# GPIO_Expander.net
KiCad netlist of a schematic drawn in Altium Designer
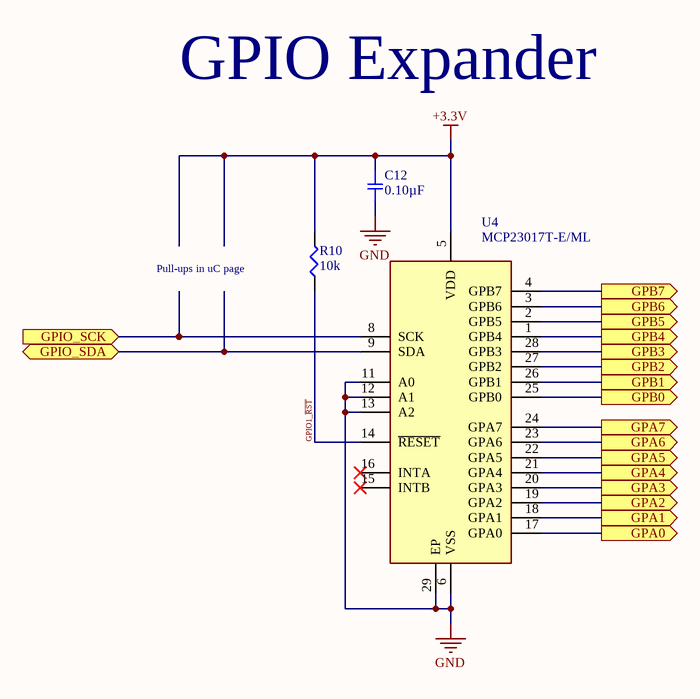
[diagram p0: GPIO_Expander.SchDoc]

(export (version "E")
  (design (tool "Eeschema 10.0.6"))
  (components
    (comp (ref "C12")
      (value "0.10µF")
      (footprint "SMD-0402C")
      (description "CAP CER 0.1UF 16V X7R 0402")
      (fields
        (field (name "DIGI-KEY PART NUMBER") "490-4759-1-ND")
        (field (name "PART NUMBER") "GCM155R71C104KA55D")
      )
      (libsource (lib "capacitor_murata_0402") (part "GCM155R71C104KA55D"))
    )
    (comp (ref "R10")
      (value "10k")
      (footprint "SMD-0402-RES")
      (description "RES SMD 10K OHM 1% 1/10W 0402")
      (fields
        (field (name "PART NUMBER") "ERJ-2RKF1002X")
        (field (name "DIGI-KEY PART NUMBER") "P10.0KLCT-ND")
      )
      (libsource (lib "Panasonic_ERJ_0402") (part "ERJ-2RKF1002X"))
    )
    (comp (ref "U4")
      (value "MCP23017T-E/ML")
      (footprint "QFN65P600X600X100-29N-D")
      (description "Interface - I/O Expanders 16bit Input/Output Exp I2C interface")
      (fields (field (name "MOUSER PART NUMBER") "579-MCP23017T-E/ML"))
      (libsource (lib "SomoPowerPackControl") (part "MCP23017T-E/ML"))
    )
  )
  (nets
    (net (code "1") (name "+3.3V") (class "Default")
      (node (ref "C12") (pin "1") (pinfunction "1_1") (pintype "passive"))
      (node (ref "R10") (pin "2") (pinfunction "2_2") (pintype "passive"))
      (node (ref "U4") (pin "5") (pinfunction "VDD_5") (pintype "passive"))
    )
    (net (code "2") (name "/GPA0") (class "Default")
      (node (ref "U4") (pin "17") (pinfunction "GPA0_17") (pintype "passive"))
    )
    (net (code "3") (name "/GPA1") (class "Default")
      (node (ref "U4") (pin "18") (pinfunction "GPA1_18") (pintype "passive"))
    )
    (net (code "4") (name "/GPA2") (class "Default")
      (node (ref "U4") (pin "19") (pinfunction "GPA2_19") (pintype "passive"))
    )
    (net (code "5") (name "/GPA3") (class "Default")
      (node (ref "U4") (pin "20") (pinfunction "GPA3_20") (pintype "passive"))
    )
    (net (code "6") (name "/GPA4") (class "Default")
      (node (ref "U4") (pin "21") (pinfunction "GPA4_21") (pintype "passive"))
    )
    (net (code "7") (name "/GPA5") (class "Default")
      (node (ref "U4") (pin "22") (pinfunction "GPA5_22") (pintype "passive"))
    )
    (net (code "8") (name "/GPA6") (class "Default")
      (node (ref "U4") (pin "23") (pinfunction "GPA6_23") (pintype "passive"))
    )
    (net (code "9") (name "/GPA7") (class "Default")
      (node (ref "U4") (pin "24") (pinfunction "GPA7_24") (pintype "passive"))
    )
    (net (code "10") (name "/GPB0") (class "Default")
      (node (ref "U4") (pin "25") (pinfunction "GPB0_25") (pintype "passive"))
    )
    (net (code "11") (name "/GPB1") (class "Default")
      (node (ref "U4") (pin "26") (pinfunction "GPB1_26") (pintype "passive"))
    )
    (net (code "12") (name "/GPB2") (class "Default")
      (node (ref "U4") (pin "27") (pinfunction "GPB2_27") (pintype "passive"))
    )
    (net (code "13") (name "/GPB3") (class "Default")
      (node (ref "U4") (pin "28") (pinfunction "GPB3_28") (pintype "passive"))
    )
    (net (code "14") (name "/GPB4") (class "Default")
      (node (ref "U4") (pin "1") (pinfunction "GPB4_1") (pintype "passive"))
    )
    (net (code "15") (name "/GPB5") (class "Default")
      (node (ref "U4") (pin "2") (pinfunction "GPB5_2") (pintype "passive"))
    )
    (net (code "16") (name "/GPB6") (class "Default")
      (node (ref "U4") (pin "3") (pinfunction "GPB6_3") (pintype "passive"))
    )
    (net (code "17") (name "/GPB7") (class "Default")
      (node (ref "U4") (pin "4") (pinfunction "GPB7_4") (pintype "passive"))
    )
    (net (code "18") (name "/GPIO1_~{RST}") (class "Default")
      (node (ref "R10") (pin "1") (pinfunction "1_1") (pintype "passive"))
      (node (ref "U4") (pin "14") (pinfunction "~{RESET}_14") (pintype "passive"))
    )
    (net (code "19") (name "/GPIO_SCK") (class "Default")
      (node (ref "U4") (pin "8") (pinfunction "SCK_8") (pintype "passive"))
    )
    (net (code "20") (name "/GPIO_SDA") (class "Default")
      (node (ref "U4") (pin "9") (pinfunction "SDA_9") (pintype "passive"))
    )
    (net (code "21") (name "GND") (class "Default")
      (node (ref "C12") (pin "2") (pinfunction "2_2") (pintype "passive"))
      (node (ref "U4") (pin "11") (pinfunction "A0_11") (pintype "passive"))
      (node (ref "U4") (pin "12") (pinfunction "A1_12") (pintype "passive"))
      (node (ref "U4") (pin "13") (pinfunction "A2_13") (pintype "passive"))
      (node (ref "U4") (pin "29") (pinfunction "EP_29") (pintype "passive"))
      (node (ref "U4") (pin "6") (pinfunction "VSS_6") (pintype "passive"))
    )
    (net (code "22") (name "unconnected-(U4-INTA-Pad16)") (class "Default")
      (node (ref "U4") (pin "16") (pinfunction "INTA_16") (pintype "passive+no_connect"))
    )
    (net (code "23") (name "unconnected-(U4-INTB-Pad15)") (class "Default")
      (node (ref "U4") (pin "15") (pinfunction "INTB_15") (pintype "passive+no_connect"))
    )
    (net (code "24") (name "unconnected-(U4-NC_1-Pad7)") (class "Default")
      (node (ref "U4") (pin "7") (pinfunction "NC_1_7") (pintype "passive"))
    )
    (net (code "25") (name "unconnected-(U4-NC_2-Pad10)") (class "Default")
      (node (ref "U4") (pin "10") (pinfunction "NC_2_10") (pintype "passive"))
    )
  )
)
